# jetson-nano.net
KiCad netlist of a schematic drawn in Altium Designer
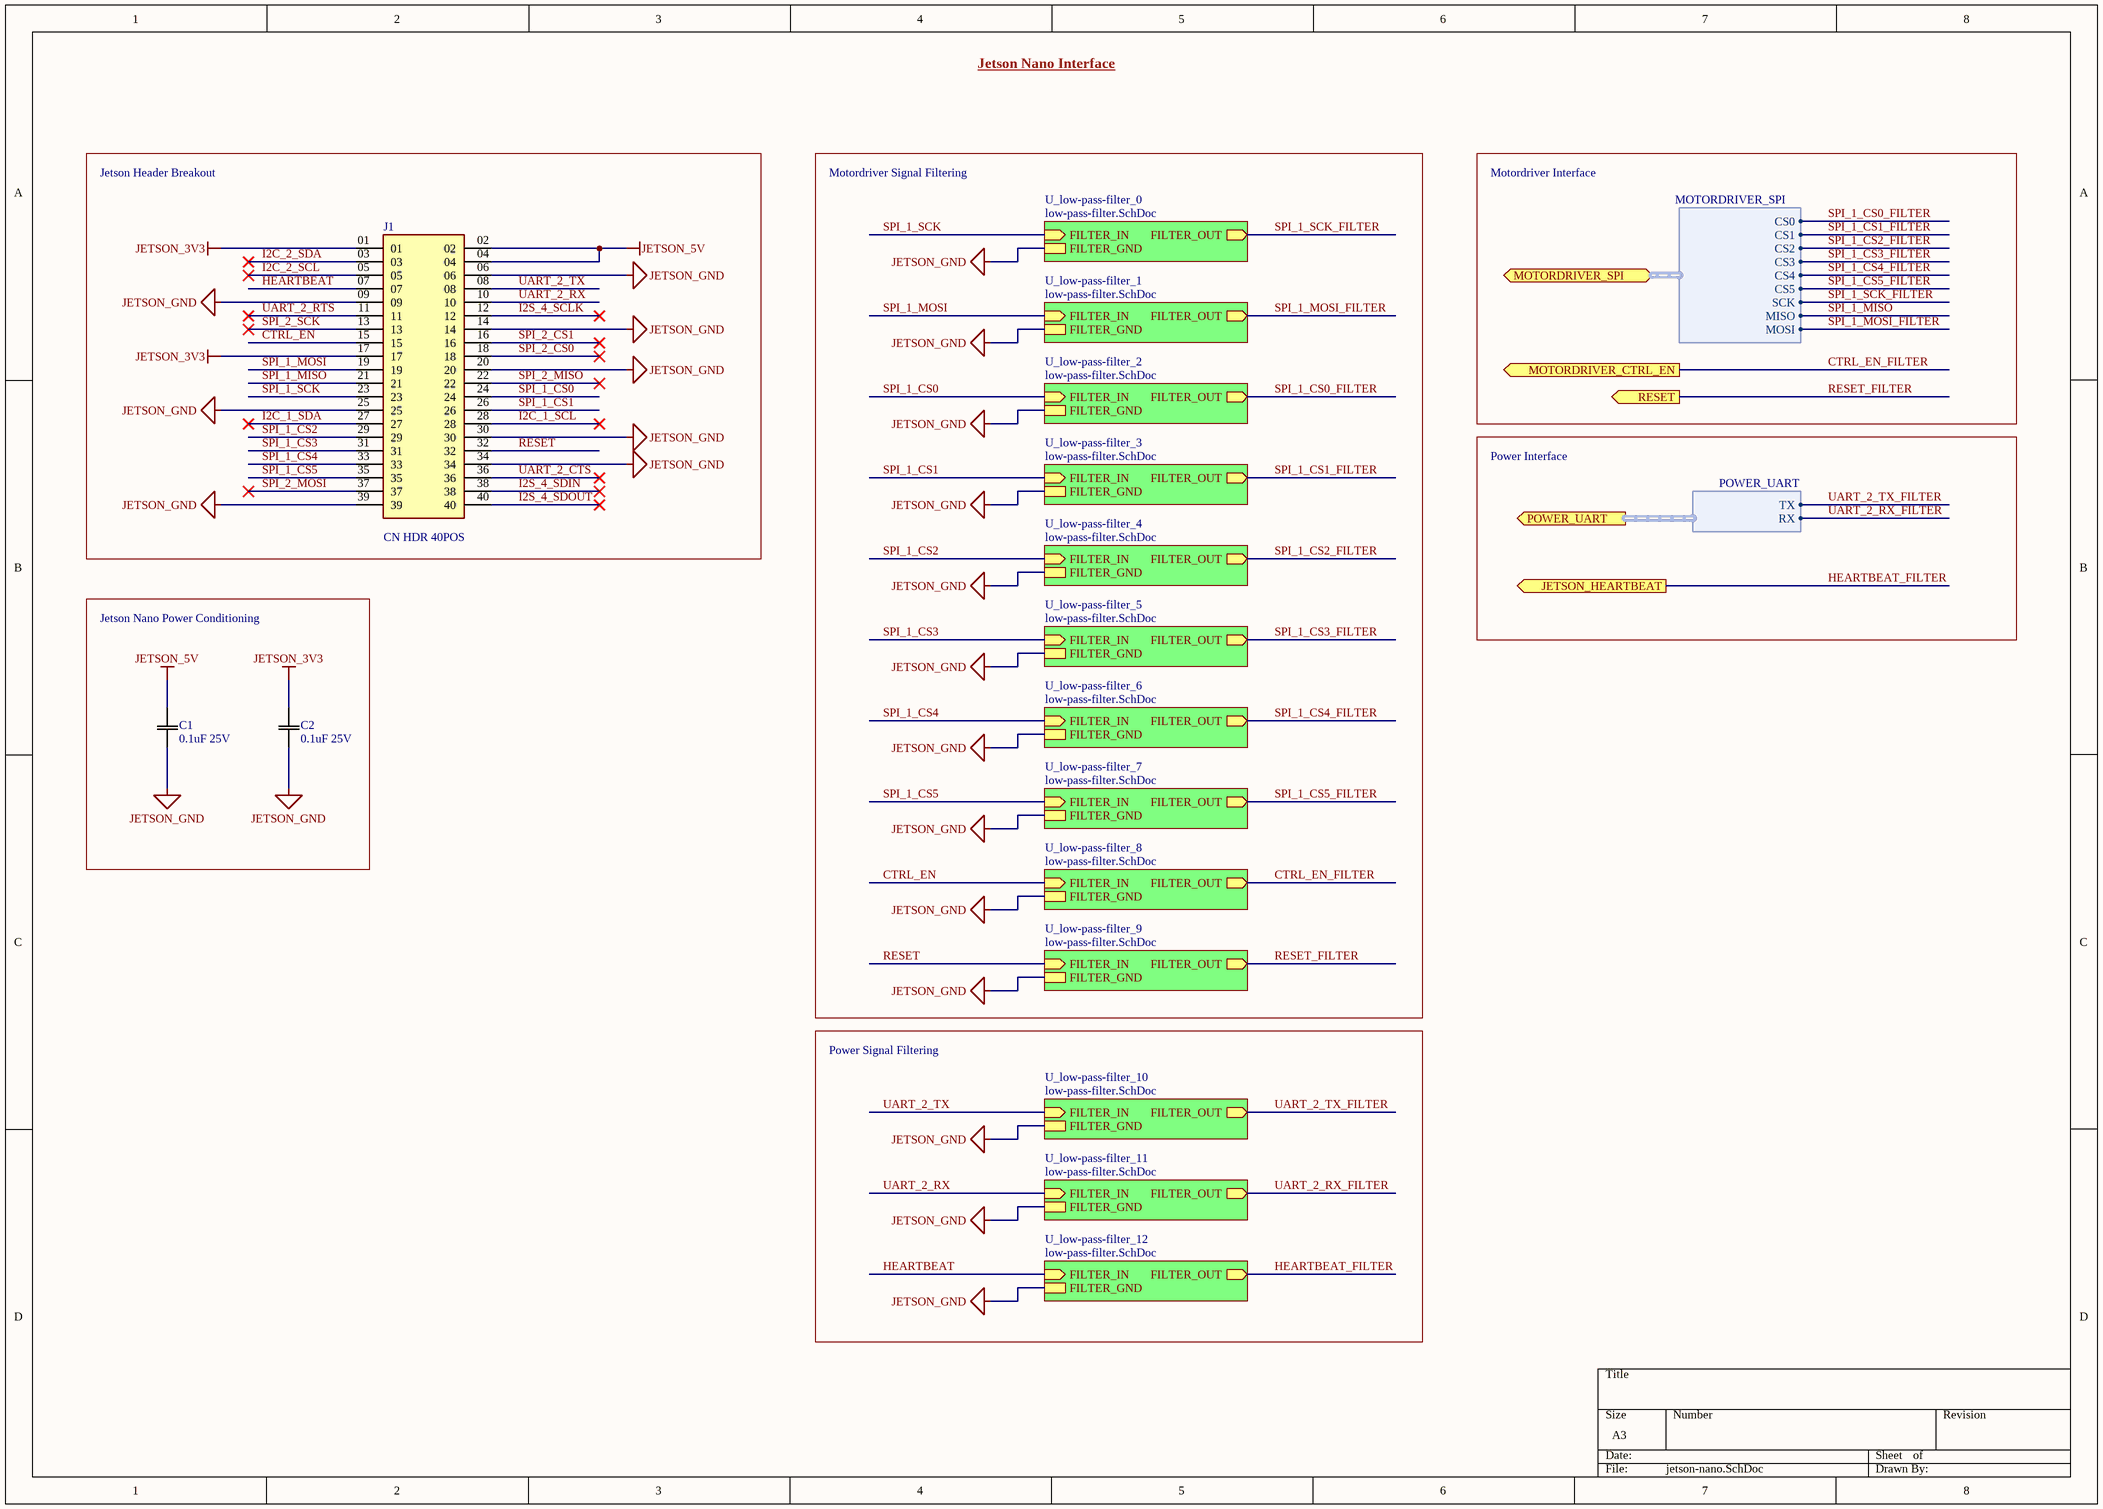
[diagram p0: jetson-nano.SchDoc]

(export (version "E")
  (design (tool "Eeschema 10.0.6"))
  (components
    (comp (ref "C1")
      (value "0.1uF 25V")
      (footprint "0805")
      (description "Default Symbol for Capacitors")
      (fields (field (name "TOLERANCE") "10%") (field (name "PART NUMBER") "CAP 0.1uF 25V"))
      (libsource (lib "Capacitor_Library") (part "CAP_Default"))
    )
    (comp (ref "C2")
      (value "0.1uF 25V")
      (footprint "0805")
      (description "Default Symbol for Capacitors")
      (fields (field (name "TOLERANCE") "10%") (field (name "PART NUMBER") "CAP 0.1uF 25V"))
      (libsource (lib "Capacitor_Library") (part "CAP_Default"))
    )
    (comp (ref "J1")
      (value "CN HDR 40POS")
      (footprint "CN HDR 40POS 0.1 TH")
      (description "40 Position Header Connector")
      (libsource (lib "Connector_Library") (part "CN HDR 40POS"))
    )
  )
  (nets
    (net (code "3") (name "/CTRL_EN") (class "Default")
      (node (ref "J1") (pin "15") (pinfunction "15_15") (pintype "passive"))
    )
    (net (code "5") (name "/HEARTBEAT") (class "Default")
      (node (ref "J1") (pin "07") (pinfunction "07_07") (pintype "passive"))
    )
    (net (code "7") (name "/I2C_1_SCL") (class "Default")
      (node (ref "J1") (pin "28") (pinfunction "28_28") (pintype "passive+no_connect"))
    )
    (net (code "8") (name "/I2C_1_SDA") (class "Default")
      (node (ref "J1") (pin "27") (pinfunction "27_27") (pintype "passive+no_connect"))
    )
    (net (code "9") (name "/I2C_2_SCL") (class "Default")
      (node (ref "J1") (pin "05") (pinfunction "05_05") (pintype "passive+no_connect"))
    )
    (net (code "10") (name "/I2C_2_SDA") (class "Default")
      (node (ref "J1") (pin "03") (pinfunction "03_03") (pintype "passive+no_connect"))
    )
    (net (code "11") (name "/I2S_4_SCLK") (class "Default")
      (node (ref "J1") (pin "12") (pinfunction "12_12") (pintype "passive+no_connect"))
    )
    (net (code "12") (name "/I2S_4_SDIN") (class "Default")
      (node (ref "J1") (pin "38") (pinfunction "38_38") (pintype "passive+no_connect"))
    )
    (net (code "13") (name "/I2S_4_SDOUT") (class "Default")
      (node (ref "J1") (pin "40") (pinfunction "40_40") (pintype "passive+no_connect"))
    )
    (net (code "14") (name "/RESET") (class "Default")
      (node (ref "J1") (pin "32") (pinfunction "32_32") (pintype "passive"))
    )
    (net (code "15") (name "/SPI_1_CS0") (class "Default")
      (node (ref "J1") (pin "24") (pinfunction "24_24") (pintype "passive"))
    )
    (net (code "17") (name "/SPI_1_CS1") (class "Default")
      (node (ref "J1") (pin "26") (pinfunction "26_26") (pintype "passive"))
    )
    (net (code "19") (name "/SPI_1_CS2") (class "Default")
      (node (ref "J1") (pin "29") (pinfunction "29_29") (pintype "passive"))
    )
    (net (code "21") (name "/SPI_1_CS3") (class "Default")
      (node (ref "J1") (pin "31") (pinfunction "31_31") (pintype "passive"))
    )
    (net (code "23") (name "/SPI_1_CS4") (class "Default")
      (node (ref "J1") (pin "33") (pinfunction "33_33") (pintype "passive"))
    )
    (net (code "25") (name "/SPI_1_CS5") (class "Default")
      (node (ref "J1") (pin "35") (pinfunction "35_35") (pintype "passive"))
    )
    (net (code "27") (name "/SPI_1_MISO") (class "Default")
      (node (ref "J1") (pin "21") (pinfunction "21_21") (pintype "passive"))
    )
    (net (code "28") (name "/SPI_1_MOSI") (class "Default")
      (node (ref "J1") (pin "19") (pinfunction "19_19") (pintype "passive"))
    )
    (net (code "30") (name "/SPI_1_SCK") (class "Default")
      (node (ref "J1") (pin "23") (pinfunction "23_23") (pintype "passive"))
    )
    (net (code "32") (name "/SPI_2_CS0") (class "Default")
      (node (ref "J1") (pin "18") (pinfunction "18_18") (pintype "passive+no_connect"))
    )
    (net (code "33") (name "/SPI_2_CS1") (class "Default")
      (node (ref "J1") (pin "16") (pinfunction "16_16") (pintype "passive+no_connect"))
    )
    (net (code "34") (name "/SPI_2_MISO") (class "Default")
      (node (ref "J1") (pin "22") (pinfunction "22_22") (pintype "passive+no_connect"))
    )
    (net (code "35") (name "/SPI_2_MOSI") (class "Default")
      (node (ref "J1") (pin "37") (pinfunction "37_37") (pintype "passive+no_connect"))
    )
    (net (code "36") (name "/SPI_2_SCK") (class "Default")
      (node (ref "J1") (pin "13") (pinfunction "13_13") (pintype "passive+no_connect"))
    )
    (net (code "37") (name "/UART_2_CTS") (class "Default")
      (node (ref "J1") (pin "36") (pinfunction "36_36") (pintype "passive+no_connect"))
    )
    (net (code "38") (name "/UART_2_RTS") (class "Default")
      (node (ref "J1") (pin "11") (pinfunction "11_11") (pintype "passive+no_connect"))
    )
    (net (code "39") (name "/UART_2_RX") (class "Default")
      (node (ref "J1") (pin "10") (pinfunction "10_10") (pintype "passive"))
    )
    (net (code "41") (name "/UART_2_TX") (class "Default")
      (node (ref "J1") (pin "08") (pinfunction "08_08") (pintype "passive"))
    )
    (net (code "45") (name "JETSON_3V3") (class "Default")
      (node (ref "C2") (pin "2") (pinfunction "C2_2") (pintype "passive"))
      (node (ref "J1") (pin "01") (pinfunction "01_01") (pintype "passive"))
      (node (ref "J1") (pin "17") (pinfunction "17_17") (pintype "passive"))
    )
    (net (code "46") (name "JETSON_5V") (class "Default")
      (node (ref "C1") (pin "2") (pinfunction "C2_2") (pintype "passive"))
      (node (ref "J1") (pin "02") (pinfunction "02_02") (pintype "passive"))
      (node (ref "J1") (pin "04") (pinfunction "04_04") (pintype "passive"))
    )
    (net (code "47") (name "JETSON_GND") (class "Default")
      (node (ref "C1") (pin "1") (pinfunction "C1_1") (pintype "passive"))
      (node (ref "C2") (pin "1") (pinfunction "C1_1") (pintype "passive"))
      (node (ref "J1") (pin "06") (pinfunction "06_06") (pintype "passive"))
      (node (ref "J1") (pin "09") (pinfunction "09_09") (pintype "passive"))
      (node (ref "J1") (pin "14") (pinfunction "14_14") (pintype "passive"))
      (node (ref "J1") (pin "20") (pinfunction "20_20") (pintype "passive"))
      (node (ref "J1") (pin "25") (pinfunction "25_25") (pintype "passive"))
      (node (ref "J1") (pin "30") (pinfunction "30_30") (pintype "passive"))
      (node (ref "J1") (pin "34") (pinfunction "34_34") (pintype "passive"))
      (node (ref "J1") (pin "39") (pinfunction "39_39") (pintype "passive"))
    )
  )
)
